# Distance_Switch_IR_and_Hall.net
KiCad netlist of a schematic drawn in Altium Designer
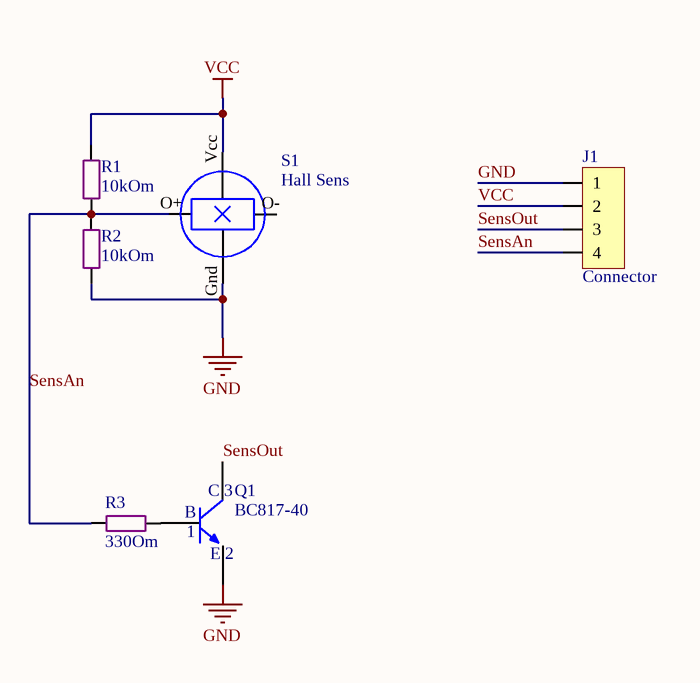
[diagram p0: Distance Switch IR and Hall.SchDoc]

(export (version "E")
  (design (tool "Eeschema 10.0.6"))
  (components
    (comp (ref "J1")
      (value "Connector")
      (footprint "Connector:Molex Micro-Fit 3.0 - 4 pin D R")
      (description "Horisontal, Dbl line, Male - 3mm")
      (fields (field (name "PART NUMBER") "0430450402"))
      (libsource (lib "Connector") (part "Micro-Fit 4R (2x2)"))
    )
    (comp (ref "Q1")
      (value "BC817-40")
      (footprint "GeneralCases:SOT-23")
      (description "NPN 45 V, 500 mA NPN general-purpose transistor")
      (libsource (lib "Transistor") (part "BC817-40"))
    )
    (comp (ref "R1")
      (value "10kOm")
      (footprint "PassiveComponents:SMD 0805 (2012)")
      (libsource (lib "PassiveComponents") (part "Res All Types"))
    )
    (comp (ref "R2")
      (value "10kOm")
      (footprint "PassiveComponents:SMD 0805 (2012)")
      (libsource (lib "PassiveComponents") (part "Res All Types"))
    )
    (comp (ref "R3")
      (value "330Om")
      (footprint "PassiveComponents:SMD 0805 (2012)")
      (libsource (lib "PassiveComponents") (part "Res All Types"))
    )
    (comp (ref "S1")
      (value "Hall Sens")
      (footprint "Sensors:Hall Sensor 3Pin")
      (libsource (lib "Sensors") (part "Hall Sensor K1116KP8"))
    )
  )
  (nets
    (net (code "1") (name "/SensAn") (class "Default")
      (node (ref "J1") (pin "4") (pinfunction "4_4") (pintype "passive"))
      (node (ref "R1") (pin "1") (pinfunction "1_1") (pintype "passive"))
      (node (ref "R2") (pin "2") (pinfunction "2_2") (pintype "passive"))
      (node (ref "R3") (pin "1") (pinfunction "1_1") (pintype "passive"))
      (node (ref "S1") (pin "O+") (pinfunction "O+_O+") (pintype "passive"))
    )
    (net (code "2") (name "/SensOut") (class "Default")
      (node (ref "J1") (pin "3") (pinfunction "3_3") (pintype "passive"))
      (node (ref "Q1") (pin "3") (pinfunction "C_3") (pintype "passive"))
    )
    (net (code "3") (name "GND") (class "Default")
      (node (ref "J1") (pin "1") (pinfunction "1_1") (pintype "passive"))
      (node (ref "Q1") (pin "2") (pinfunction "E_2") (pintype "passive"))
      (node (ref "R2") (pin "1") (pinfunction "1_1") (pintype "passive"))
      (node (ref "S1") (pin "Gnd") (pinfunction "Gnd_Gnd") (pintype "passive"))
    )
    (net (code "4") (name "Net-(Q1-B)") (class "Default")
      (node (ref "Q1") (pin "1") (pinfunction "B_1") (pintype "passive"))
      (node (ref "R3") (pin "2") (pinfunction "2_2") (pintype "passive"))
    )
    (net (code "5") (name "VCC") (class "Default")
      (node (ref "J1") (pin "2") (pinfunction "2_2") (pintype "passive"))
      (node (ref "R1") (pin "2") (pinfunction "2_2") (pintype "passive"))
      (node (ref "S1") (pin "Vcc") (pinfunction "Vcc_Vcc") (pintype "passive"))
    )
    (net (code "6") (name "unconnected-(S1-PadO-)") (class "Default")
      (node (ref "S1") (pin "O-") (pinfunction "O-_O-") (pintype "passive"))
    )
  )
)
